# boneX_led_strip.net
KiCad netlist of a schematic drawn in EAGLE
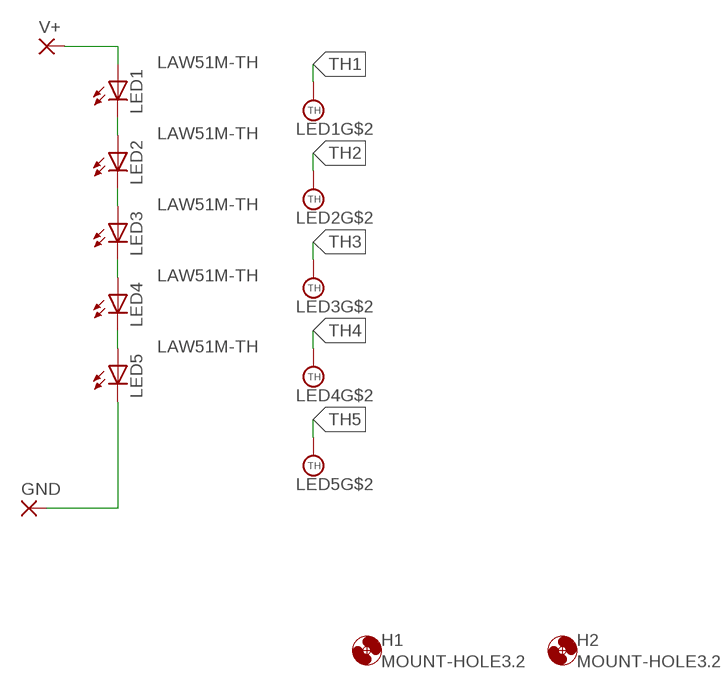
[diagram p0: schematic, sheet 1]

(export (version "E")
  (design (tool "Eeschema 10.0.6"))
  (components
    (comp (ref "GND")
      (value "SMD5")
      (footprint "eagle-import:SMD2,54-5,08")
      (libsource (lib "eagle-import") (part "SMD5"))
    )
    (comp (ref "H1")
      (value "MOUNT-HOLE3.2")
      (footprint "eagle-import:3,2")
      (libsource (lib "eagle-import") (part "MOUNT-HOLE3.2"))
    )
    (comp (ref "H2")
      (value "MOUNT-HOLE3.2")
      (footprint "eagle-import:3,2")
      (libsource (lib "eagle-import") (part "MOUNT-HOLE3.2"))
    )
    (comp (ref "LED1")
      (value "LAW51M-TH")
      (footprint "eagle-import:W51-COOL")
      (libsource (lib "eagle-import") (part "W51M-THLA"))
    )
    (comp (ref "LED2")
      (value "LAW51M-TH")
      (footprint "eagle-import:W51-COOL")
      (libsource (lib "eagle-import") (part "W51M-THLA"))
    )
    (comp (ref "LED3")
      (value "LAW51M-TH")
      (footprint "eagle-import:W51-COOL")
      (libsource (lib "eagle-import") (part "W51M-THLA"))
    )
    (comp (ref "LED4")
      (value "LAW51M-TH")
      (footprint "eagle-import:W51-COOL")
      (libsource (lib "eagle-import") (part "W51M-THLA"))
    )
    (comp (ref "LED5")
      (value "LAW51M-TH")
      (footprint "eagle-import:W51-COOL")
      (libsource (lib "eagle-import") (part "W51M-THLA"))
    )
    (comp (ref "V+")
      (value "SMD5")
      (footprint "eagle-import:SMD2,54-5,08")
      (libsource (lib "eagle-import") (part "SMD5"))
    )
  )
  (nets
    (net (code "1") (name "Net-(GND-P)") (class "Default")
      (node (ref "GND") (pin "1") (pinfunction "P_1") (pintype "passive"))
      (node (ref "LED5") (pin "C") (pinfunction "C_C") (pintype "passive"))
    )
    (net (code "2") (name "Net-(LED1-PadC)") (class "Default")
      (node (ref "LED1") (pin "C") (pinfunction "C_C") (pintype "passive"))
      (node (ref "LED2") (pin "A") (pinfunction "A_A") (pintype "passive"))
    )
    (net (code "3") (name "Net-(LED2-PadC)") (class "Default")
      (node (ref "LED2") (pin "C") (pinfunction "C_C") (pintype "passive"))
      (node (ref "LED3") (pin "A") (pinfunction "A_A") (pintype "passive"))
    )
    (net (code "4") (name "Net-(LED3-PadC)") (class "Default")
      (node (ref "LED3") (pin "C") (pinfunction "C_C") (pintype "passive"))
      (node (ref "LED4") (pin "A") (pinfunction "A_A") (pintype "passive"))
    )
    (net (code "5") (name "Net-(LED4-PadC)") (class "Default")
      (node (ref "LED4") (pin "C") (pinfunction "C_C") (pintype "passive"))
      (node (ref "LED5") (pin "A") (pinfunction "A_A") (pintype "passive"))
    )
    (net (code "6") (name "Net-(V+-P)") (class "Default")
      (node (ref "LED1") (pin "A") (pinfunction "A_A") (pintype "passive"))
      (node (ref "V+") (pin "1") (pinfunction "P_1") (pintype "passive"))
    )
    (net (code "7") (name "TH1") (class "Default")
      (node (ref "LED1") (pin "TH@1") (pinfunction "TH_TH@1") (pintype "passive"))
      (node (ref "LED1") (pin "TH@10") (pinfunction "TH_TH@10") (pintype "passive"))
      (node (ref "LED1") (pin "TH@11") (pinfunction "TH_TH@11") (pintype "passive"))
      (node (ref "LED1") (pin "TH@12") (pinfunction "TH_TH@12") (pintype "passive"))
      (node (ref "LED1") (pin "TH@2") (pinfunction "TH_TH@2") (pintype "passive"))
      (node (ref "LED1") (pin "TH@3") (pinfunction "TH_TH@3") (pintype "passive"))
      (node (ref "LED1") (pin "TH@4") (pinfunction "TH_TH@4") (pintype "passive"))
      (node (ref "LED1") (pin "TH@5") (pinfunction "TH_TH@5") (pintype "passive"))
      (node (ref "LED1") (pin "TH@6") (pinfunction "TH_TH@6") (pintype "passive"))
      (node (ref "LED1") (pin "TH@7") (pinfunction "TH_TH@7") (pintype "passive"))
      (node (ref "LED1") (pin "TH@8") (pinfunction "TH_TH@8") (pintype "passive"))
      (node (ref "LED1") (pin "TH@9") (pinfunction "TH_TH@9") (pintype "passive"))
    )
    (net (code "8") (name "TH2") (class "Default")
      (node (ref "LED2") (pin "TH@1") (pinfunction "TH_TH@1") (pintype "passive"))
      (node (ref "LED2") (pin "TH@10") (pinfunction "TH_TH@10") (pintype "passive"))
      (node (ref "LED2") (pin "TH@11") (pinfunction "TH_TH@11") (pintype "passive"))
      (node (ref "LED2") (pin "TH@12") (pinfunction "TH_TH@12") (pintype "passive"))
      (node (ref "LED2") (pin "TH@2") (pinfunction "TH_TH@2") (pintype "passive"))
      (node (ref "LED2") (pin "TH@3") (pinfunction "TH_TH@3") (pintype "passive"))
      (node (ref "LED2") (pin "TH@4") (pinfunction "TH_TH@4") (pintype "passive"))
      (node (ref "LED2") (pin "TH@5") (pinfunction "TH_TH@5") (pintype "passive"))
      (node (ref "LED2") (pin "TH@6") (pinfunction "TH_TH@6") (pintype "passive"))
      (node (ref "LED2") (pin "TH@7") (pinfunction "TH_TH@7") (pintype "passive"))
      (node (ref "LED2") (pin "TH@8") (pinfunction "TH_TH@8") (pintype "passive"))
      (node (ref "LED2") (pin "TH@9") (pinfunction "TH_TH@9") (pintype "passive"))
    )
    (net (code "9") (name "TH3") (class "Default")
      (node (ref "LED3") (pin "TH@1") (pinfunction "TH_TH@1") (pintype "passive"))
      (node (ref "LED3") (pin "TH@10") (pinfunction "TH_TH@10") (pintype "passive"))
      (node (ref "LED3") (pin "TH@11") (pinfunction "TH_TH@11") (pintype "passive"))
      (node (ref "LED3") (pin "TH@12") (pinfunction "TH_TH@12") (pintype "passive"))
      (node (ref "LED3") (pin "TH@2") (pinfunction "TH_TH@2") (pintype "passive"))
      (node (ref "LED3") (pin "TH@3") (pinfunction "TH_TH@3") (pintype "passive"))
      (node (ref "LED3") (pin "TH@4") (pinfunction "TH_TH@4") (pintype "passive"))
      (node (ref "LED3") (pin "TH@5") (pinfunction "TH_TH@5") (pintype "passive"))
      (node (ref "LED3") (pin "TH@6") (pinfunction "TH_TH@6") (pintype "passive"))
      (node (ref "LED3") (pin "TH@7") (pinfunction "TH_TH@7") (pintype "passive"))
      (node (ref "LED3") (pin "TH@8") (pinfunction "TH_TH@8") (pintype "passive"))
      (node (ref "LED3") (pin "TH@9") (pinfunction "TH_TH@9") (pintype "passive"))
    )
    (net (code "10") (name "TH4") (class "Default")
      (node (ref "LED4") (pin "TH@1") (pinfunction "TH_TH@1") (pintype "passive"))
      (node (ref "LED4") (pin "TH@10") (pinfunction "TH_TH@10") (pintype "passive"))
      (node (ref "LED4") (pin "TH@11") (pinfunction "TH_TH@11") (pintype "passive"))
      (node (ref "LED4") (pin "TH@12") (pinfunction "TH_TH@12") (pintype "passive"))
      (node (ref "LED4") (pin "TH@2") (pinfunction "TH_TH@2") (pintype "passive"))
      (node (ref "LED4") (pin "TH@3") (pinfunction "TH_TH@3") (pintype "passive"))
      (node (ref "LED4") (pin "TH@4") (pinfunction "TH_TH@4") (pintype "passive"))
      (node (ref "LED4") (pin "TH@5") (pinfunction "TH_TH@5") (pintype "passive"))
      (node (ref "LED4") (pin "TH@6") (pinfunction "TH_TH@6") (pintype "passive"))
      (node (ref "LED4") (pin "TH@7") (pinfunction "TH_TH@7") (pintype "passive"))
      (node (ref "LED4") (pin "TH@8") (pinfunction "TH_TH@8") (pintype "passive"))
      (node (ref "LED4") (pin "TH@9") (pinfunction "TH_TH@9") (pintype "passive"))
    )
    (net (code "11") (name "TH5") (class "Default")
      (node (ref "LED5") (pin "TH@1") (pinfunction "TH_TH@1") (pintype "passive"))
      (node (ref "LED5") (pin "TH@10") (pinfunction "TH_TH@10") (pintype "passive"))
      (node (ref "LED5") (pin "TH@11") (pinfunction "TH_TH@11") (pintype "passive"))
      (node (ref "LED5") (pin "TH@12") (pinfunction "TH_TH@12") (pintype "passive"))
      (node (ref "LED5") (pin "TH@2") (pinfunction "TH_TH@2") (pintype "passive"))
      (node (ref "LED5") (pin "TH@3") (pinfunction "TH_TH@3") (pintype "passive"))
      (node (ref "LED5") (pin "TH@4") (pinfunction "TH_TH@4") (pintype "passive"))
      (node (ref "LED5") (pin "TH@5") (pinfunction "TH_TH@5") (pintype "passive"))
      (node (ref "LED5") (pin "TH@6") (pinfunction "TH_TH@6") (pintype "passive"))
      (node (ref "LED5") (pin "TH@7") (pinfunction "TH_TH@7") (pintype "passive"))
      (node (ref "LED5") (pin "TH@8") (pinfunction "TH_TH@8") (pintype "passive"))
      (node (ref "LED5") (pin "TH@9") (pinfunction "TH_TH@9") (pintype "passive"))
    )
  )
)
